# esc_inputs.net
KiCad netlist of a schematic drawn in Altium Designer
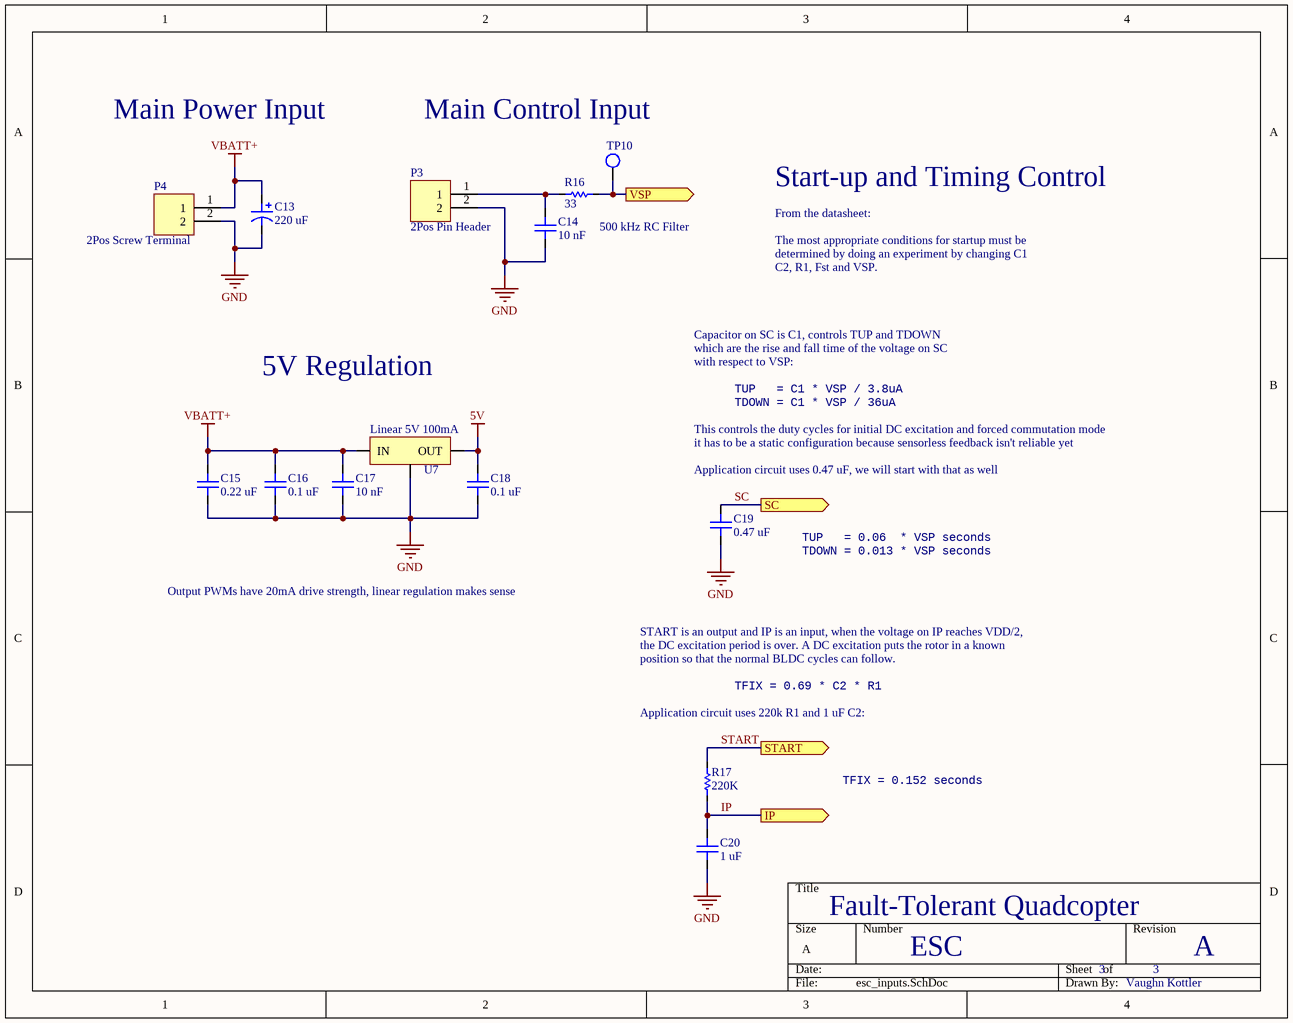
[diagram p0: esc_inputs.SchDoc]

(export (version "E")
  (design (tool "Eeschema 10.0.6"))
  (components
    (comp (ref "C13")
      (value "220 uF")
      (footprint "CAP-CAN-8.3x8.3")
      (description "±20%, 8.3mm x 8.3mm")
      (libsource (lib "passive") (part "CAP-CAN-220uF-35V"))
    )
    (comp (ref "C14")
      (value "10 nF")
      (footprint "CAP-CER-0805-SHORT")
      (description "10%, 0805")
      (libsource (lib "passive") (part "CAP-CER-10nF-50V"))
    )
    (comp (ref "C15")
      (value "0.22 uF")
      (footprint "CAP-CER-0805-SHORT")
      (description "10%, 0805")
      (libsource (lib "passive") (part "CAP-CER-0.22uF-50V"))
    )
    (comp (ref "C16")
      (value "0.1 uF")
      (footprint "CAP-CER-0805-SHORT")
      (description "10%, 0805")
      (libsource (lib "passive") (part "CAP-CER-0.1uF-25V"))
    )
    (comp (ref "C17")
      (value "10 nF")
      (footprint "CAP-CER-0805-SHORT")
      (description "±10%, 0805")
      (libsource (lib "passive") (part "CAP-CER-10nF-50V"))
    )
    (comp (ref "C18")
      (value "0.1 uF")
      (footprint "CAP-CER-0805-SHORT")
      (description "10%, 0805")
      (libsource (lib "passive") (part "CAP-CER-0.1uF-25V"))
    )
    (comp (ref "C19")
      (value "0.47 uF")
      (footprint "CAP-CER-0805-TALL")
      (description "±10%, 0805")
      (libsource (lib "passive") (part "CAP-CER-0.47uF-50V"))
    )
    (comp (ref "C20")
      (value "1 uF")
      (footprint "CAP-CER-0805-TALL")
      (description "±10%, 0805")
      (libsource (lib "passive") (part "CAP-CER-1uF-10V"))
    )
    (comp (ref "P3")
      (value "2Pos Pin Header")
      (footprint "2Pos Pin Header F RA R")
      (description "0.1\" Pitch 1x2")
      (libsource (lib "connector") (part "2Pos Pin Header"))
    )
    (comp (ref "P4")
      (value "2Pos Screw Terminal")
      (footprint "2Pos Screw Terminal")
      (description "0.2\" Pitch 1x2")
      (libsource (lib "connector") (part "2Pos Screw Terminal"))
    )
    (comp (ref "R16")
      (value "33")
      (footprint "RES-0805")
      (description "0805")
      (libsource (lib "passive") (part "RES-33-1/8W"))
    )
    (comp (ref "R17")
      (value "220K")
      (footprint "RES-0805")
      (description "0805")
      (libsource (lib "passive") (part "RES-220K-1/8W"))
    )
    (comp (ref "TP10")
      (value "Test Point")
      (footprint "0603 Test Point")
      (description "0603")
      (libsource (lib "passive") (part "Test Point"))
    )
    (comp (ref "U7")
      (value "Linear 5V 100mA")
      (footprint "SOT-89")
      (description "Linear Regulator, 5V, 100mA")
      (libsource (lib "ic") (part "L78L05ACUTR"))
    )
  )
  (nets
    (net (code "1") (name "/IP") (class "Default")
      (node (ref "C20") (pin "2") (pinfunction "2_2") (pintype "passive"))
      (node (ref "R17") (pin "1") (pinfunction "1_1") (pintype "passive"))
    )
    (net (code "2") (name "/SC") (class "Default")
      (node (ref "C19") (pin "2") (pinfunction "2_2") (pintype "passive"))
    )
    (net (code "3") (name "/START") (class "Default")
      (node (ref "R17") (pin "2") (pinfunction "2_2") (pintype "passive"))
    )
    (net (code "4") (name "/VSP") (class "Default")
      (node (ref "R16") (pin "2") (pinfunction "2_2") (pintype "passive"))
      (node (ref "TP10") (pin "1") (pinfunction "1_1") (pintype "passive"))
    )
    (net (code "5") (name "5V") (class "Default")
      (node (ref "C18") (pin "2") (pinfunction "2_2") (pintype "passive"))
      (node (ref "U7") (pin "1") (pinfunction "OUT_1") (pintype "passive"))
    )
    (net (code "6") (name "GND") (class "Default")
      (node (ref "C13") (pin "2") (pinfunction "2_2") (pintype "passive"))
      (node (ref "C14") (pin "1") (pinfunction "1_1") (pintype "passive"))
      (node (ref "C15") (pin "1") (pinfunction "1_1") (pintype "passive"))
      (node (ref "C16") (pin "1") (pinfunction "1_1") (pintype "passive"))
      (node (ref "C17") (pin "1") (pinfunction "1_1") (pintype "passive"))
      (node (ref "C18") (pin "1") (pinfunction "1_1") (pintype "passive"))
      (node (ref "C19") (pin "1") (pinfunction "1_1") (pintype "passive"))
      (node (ref "C20") (pin "1") (pinfunction "1_1") (pintype "passive"))
      (node (ref "P3") (pin "2") (pinfunction "2_2") (pintype "passive"))
      (node (ref "P4") (pin "2") (pinfunction "2_2") (pintype "passive"))
      (node (ref "U7") (pin "2") (pinfunction "GND_2") (pintype "passive"))
    )
    (net (code "7") (name "Net-(C14-Pad2)") (class "Default")
      (node (ref "C14") (pin "2") (pinfunction "2_2") (pintype "passive"))
      (node (ref "P3") (pin "1") (pinfunction "1_1") (pintype "passive"))
      (node (ref "R16") (pin "1") (pinfunction "1_1") (pintype "passive"))
    )
    (net (code "8") (name "VBATT+") (class "Default")
      (node (ref "C13") (pin "1") (pinfunction "1_1") (pintype "passive"))
      (node (ref "C15") (pin "2") (pinfunction "2_2") (pintype "passive"))
      (node (ref "C16") (pin "2") (pinfunction "2_2") (pintype "passive"))
      (node (ref "C17") (pin "2") (pinfunction "2_2") (pintype "passive"))
      (node (ref "P4") (pin "1") (pinfunction "1_1") (pintype "passive"))
      (node (ref "U7") (pin "3") (pinfunction "IN_3") (pintype "passive"))
    )
  )
)
